# FRONT_MCU.net
KiCad netlist of a schematic drawn in Altium Designer
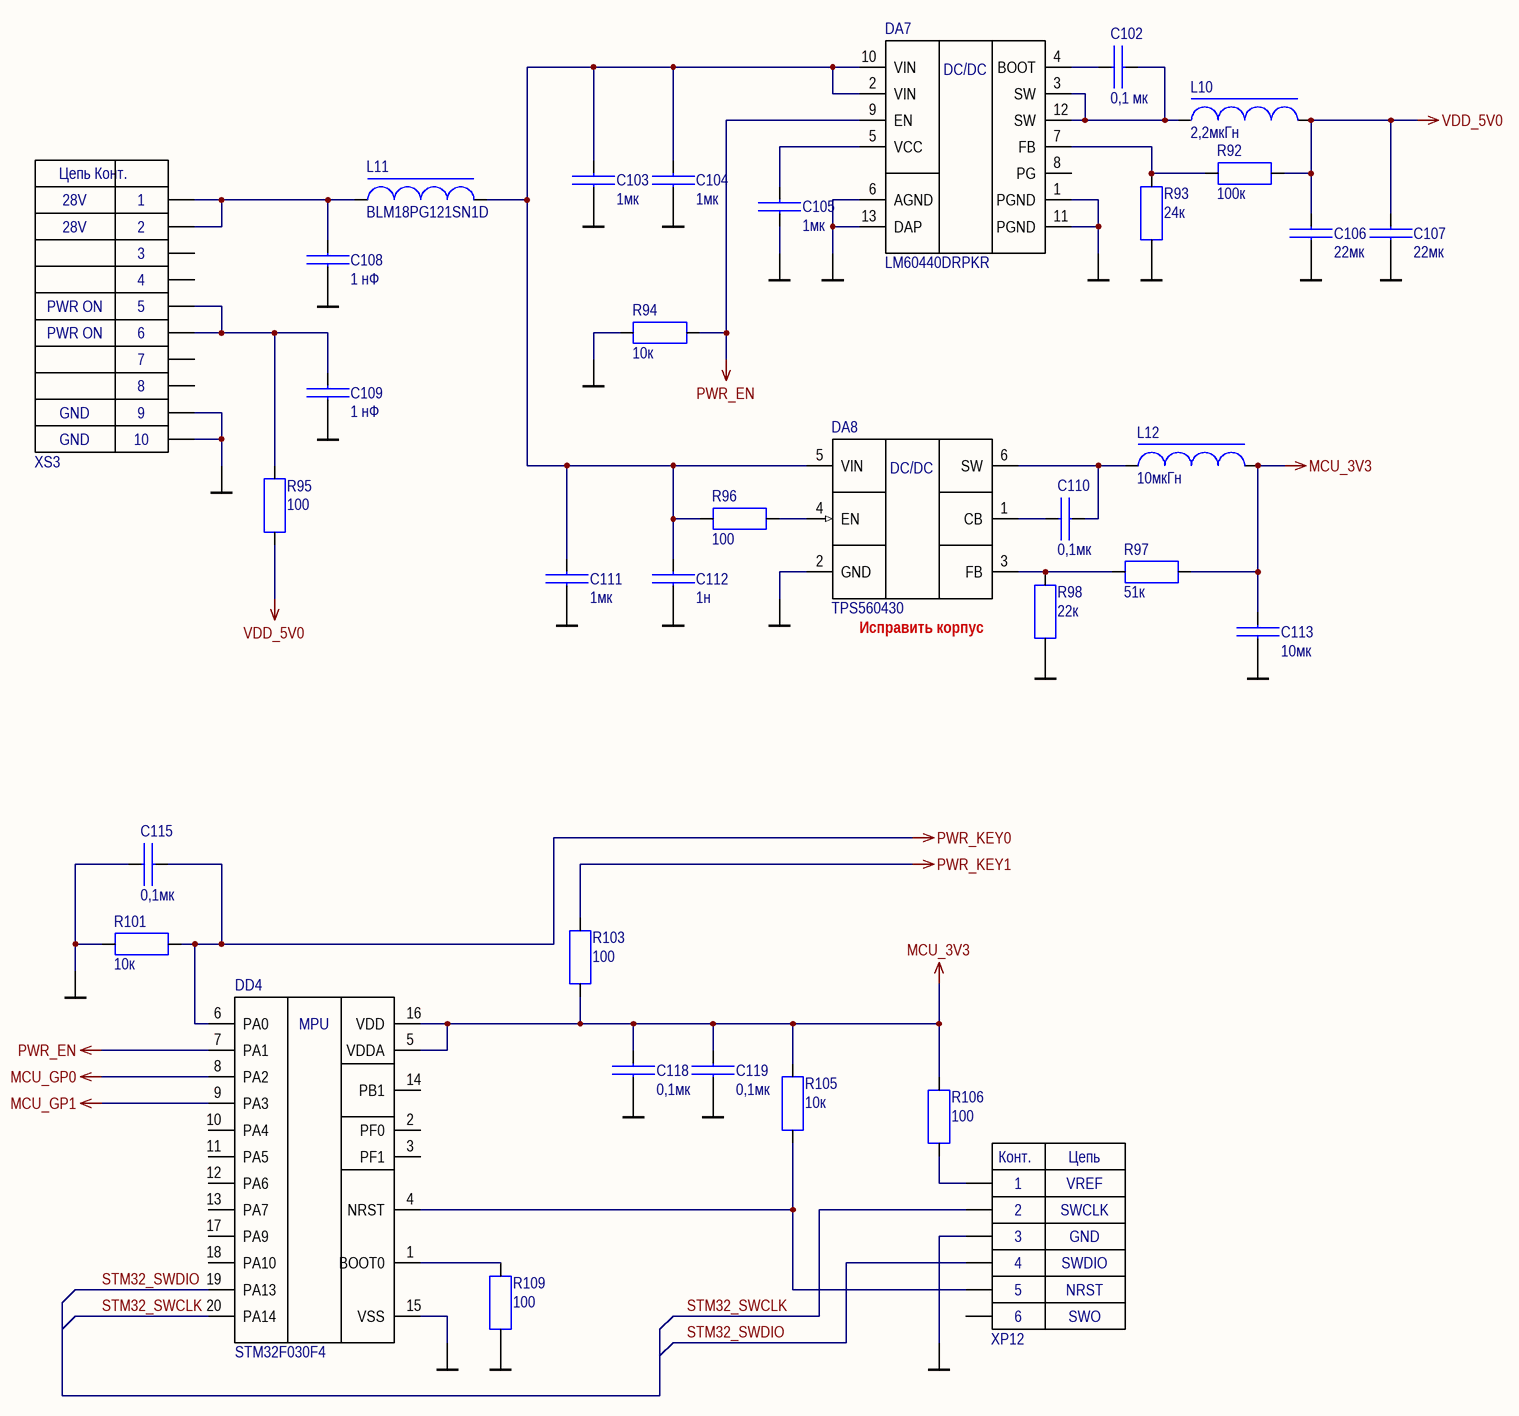
[diagram p0: FRONT_MCU.SchDoc]

(export (version "E")
  (design (tool "Eeschema 10.0.6"))
  (components
    (comp (ref "C102")
      (value "CC0402KRX5R6BB104")
      (footprint "CAPC1005X05L")
      (description "ЧИП конденсатор")
      (fields
        (field (name "NOMINAL") "0,1 мк")
        (field (name "MANUFACTURER") "Yageo")
        (field (name "TOLERANCE") "10%")
      )
      (libsource (lib "Database_Gost") (part "Capacitor const"))
    )
    (comp (ref "C103")
      (value "CC0805KKX7R9BB105")
      (footprint "CAPC2012X09L")
      (description "ЧИП конденсатор")
      (fields
        (field (name "NOMINAL") "1мк")
        (field (name "MANUFACTURER") "Yageo")
        (field (name "TOLERANCE") "0,1")
      )
      (libsource (lib "Database_Gost") (part "Capacitor const"))
    )
    (comp (ref "C104")
      (value "CC0805KKX7R9BB105")
      (footprint "CAPC2012X09L")
      (description "ЧИП конденсатор")
      (fields
        (field (name "NOMINAL") "1мк")
        (field (name "MANUFACTURER") "Yageo")
        (field (name "TOLERANCE") "0,1")
      )
      (libsource (lib "Database_Gost") (part "Capacitor const"))
    )
    (comp (ref "C105")
      (value "CC0402KRX5R5BB105")
      (footprint "CAPC1005X05L")
      (description "ЧИП конденсатор")
      (fields
        (field (name "NOMINAL") "1мк")
        (field (name "MANUFACTURER") "Yageo")
        (field (name "TOLERANCE") "10%")
      )
      (libsource (lib "Database_Gost") (part "Capacitor const"))
    )
    (comp (ref "C106")
      (value "CC0805MKX5R5BB226")
      (footprint "CAPC2012X09L")
      (description "ЧИП конденсатор")
      (fields
        (field (name "NOMINAL") "22мк")
        (field (name "MANUFACTURER") "Yageo")
        (field (name "TOLERANCE") "0,2")
      )
      (libsource (lib "Database_Gost") (part "Capacitor const"))
    )
    (comp (ref "C107")
      (value "CC0805MKX5R5BB226")
      (footprint "CAPC2012X09L")
      (description "ЧИП конденсатор")
      (fields
        (field (name "NOMINAL") "22мк")
        (field (name "MANUFACTURER") "Yageo")
        (field (name "TOLERANCE") "0,2")
      )
      (libsource (lib "Database_Gost") (part "Capacitor const"))
    )
    (comp (ref "C108")
      (value "~")
      (footprint "CAPC1005X05L")
      (description "ЧИП конденсатор")
      (fields
        (field (name "NOMINAL") "1 нФ")
        (field (name "MANUFACTURER") "Yageo")
        (field (name "MANUFACTURERPARTNUMBER") "C0402C102J5GACTU")
      )
      (libsource (lib "Database_Gost") (part "Capacitor const"))
    )
    (comp (ref "C109")
      (value "~")
      (footprint "CAPC1005X05L")
      (description "ЧИП конденсатор")
      (fields
        (field (name "NOMINAL") "1 нФ")
        (field (name "MANUFACTURER") "Yageo")
        (field (name "MANUFACTURERPARTNUMBER") "C0402C102J5GACTU")
      )
      (libsource (lib "Database_Gost") (part "Capacitor const"))
    )
    (comp (ref "C110")
      (value "CC0603KRX7R9BB103")
      (footprint "CAPC1608X08L")
      (description "ЧИП конденсатор")
      (fields
        (field (name "NOMINAL") "0,1мк")
        (field (name "MANUFACTURER") "Yageo")
        (field (name "TOLERANCE") "10%")
      )
      (libsource (lib "Database_Gost") (part "Capacitor const"))
    )
    (comp (ref "C111")
      (value "CC0805KKX7R9BB105")
      (footprint "CAPC2012X09L")
      (description "ЧИП конденсатор")
      (fields
        (field (name "NOMINAL") "1мк")
        (field (name "MANUFACTURER") "Yageo")
        (field (name "TOLERANCE") "0,1")
      )
      (libsource (lib "Database_Gost") (part "Capacitor const"))
    )
    (comp (ref "C112")
      (value "C0402C102J5GACTU")
      (footprint "CAPC1005X05L")
      (description "ЧИП конденсатор")
      (fields
        (field (name "NOMINAL") "1н")
        (field (name "MANUFACTURER") "Yageo")
        (field (name "TOLERANCE") "5%")
      )
      (libsource (lib "Database_Gost") (part "Capacitor const"))
    )
    (comp (ref "C113")
      (value "CC0805KKX5R8BB106")
      (footprint "CAPC2012X09L")
      (description "ЧИП конденсатор")
      (fields
        (field (name "NOMINAL") "10мк")
        (field (name "MANUFACTURER") "Yageo")
        (field (name "TOLERANCE") "0,1")
      )
      (libsource (lib "Database_Gost") (part "Capacitor const"))
    )
    (comp (ref "C115")
      (value "CC0402KRX5R6BB104")
      (footprint "CAPC1005X05L")
      (description "ЧИП конденсатор")
      (fields
        (field (name "NOMINAL") "0,1мк")
        (field (name "MANUFACTURER") "Yageo")
        (field (name "TOLERANCE") "10%")
      )
      (libsource (lib "Database_Gost") (part "Capacitor const"))
    )
    (comp (ref "C118")
      (value "CC0402KRX5R6BB104")
      (footprint "CAPC1005X05L")
      (description "ЧИП конденсатор")
      (fields
        (field (name "NOMINAL") "0,1мк")
        (field (name "MANUFACTURER") "Yageo")
        (field (name "TOLERANCE") "10%")
      )
      (libsource (lib "Database_Gost") (part "Capacitor const"))
    )
    (comp (ref "C119")
      (value "CC0402KRX5R6BB104")
      (footprint "CAPC1005X05L")
      (description "ЧИП конденсатор")
      (fields
        (field (name "NOMINAL") "0,1мк")
        (field (name "MANUFACTURER") "Yageo")
        (field (name "TOLERANCE") "10%")
      )
      (libsource (lib "Database_Gost") (part "Capacitor const"))
    )
    (comp (ref "DA7")
      (value "LM60440DRPKR")
      (footprint "WQFN-13")
      (description "3.8-V to 36-V, 4-A Ultra-Small Synchronous Step-Down Converter")
      (fields (field (name "MANUFACTURER") "TI"))
      (libsource (lib "Chips_single") (part "LM60440DRPKR"))
    )
    (comp (ref "DA8")
      (value "TPS560430")
      (footprint "TSOP65P280X110-8L")
      (description "SIMPLE SWITCHER® 4-V to 36-V, 600-mA Synchronous Step-Down Converter")
      (fields (field (name "MANUFACTURER") "TI"))
      (libsource (lib "Chips_single") (part "TPS560430"))
    )
    (comp (ref "DD4")
      (value "STM32F030F4")
      (footprint "TSOP65P640X120-20L")
      (fields (field (name "MANUFACTURER") "STM"))
      (libsource (lib "Chips_single") (part "STM32F030F4"))
    )
    (comp (ref "L10")
      (value "XGL4020-222ME")
      (footprint "INDCXGL4020")
      (description "Shielded Power Inductors")
      (fields (field (name "NOMINAL") "2,2мкГн") (field (name "MANUFACTURER") "Coilcraft"))
      (libsource (lib "Database_Gost") (part "Inductor ferr"))
    )
    (comp (ref "L11")
      (value "BLM18PG121SN1D")
      (footprint "INDC1608X05L")
      (description "Chip Ferrite Beads (0603 Size)")
      (fields (field (name "NOMINAL") "BLM18PG121SN1D") (field (name "MANUFACTURER") "Murata"))
      (libsource (lib "Database_Gost") (part "Inductor ferr"))
    )
    (comp (ref "L12")
      (value "1812PS-103KR")
      (footprint "INDC1812PS")
      (description "Shielded High SRF Inductors")
      (fields (field (name "NOMINAL") "10мкГн") (field (name "MANUFACTURER") "Coilcraft"))
      (libsource (lib "Database_Gost") (part "Inductor ferr"))
    )
    (comp (ref "R92")
      (value "RC0402JR-07100KL")
      (footprint "RESC1005X04L")
      (description "ЧИП резистор")
      (fields
        (field (name "NOMINAL") "100к")
        (field (name "MANUFACTURER") "Yageo")
        (field (name "TOLERANCE") "5%")
      )
      (libsource (lib "Database_Gost") (part "Resistor const"))
    )
    (comp (ref "R93")
      (value "RC0402JR-0724KL")
      (footprint "RESC1005X04L")
      (description "ЧИП резистор")
      (fields
        (field (name "NOMINAL") "24к")
        (field (name "MANUFACTURER") "Yageo")
        (field (name "TOLERANCE") "5%")
      )
      (libsource (lib "Database_Gost") (part "Resistor const"))
    )
    (comp (ref "R94")
      (value "RC0402JR-0710KL")
      (footprint "RESC1005X04L")
      (description "ЧИП резистор")
      (fields
        (field (name "NOMINAL") "10к")
        (field (name "MANUFACTURER") "Yageo")
        (field (name "TOLERANCE") "5%")
      )
      (libsource (lib "Database_Gost") (part "Resistor const"))
    )
    (comp (ref "R95")
      (value "RC0402JR-07100RL")
      (footprint "RESC1005X04L")
      (description "ЧИП резистор")
      (fields
        (field (name "NOMINAL") "100")
        (field (name "MANUFACTURER") "Yageo")
        (field (name "TOLERANCE") "5%")
      )
      (libsource (lib "Database_Gost") (part "Resistor const"))
    )
    (comp (ref "R96")
      (value "RC0402JR-07100RL")
      (footprint "RESC1005X04L")
      (description "ЧИП резистор")
      (fields
        (field (name "NOMINAL") "100")
        (field (name "MANUFACTURER") "Yageo")
        (field (name "TOLERANCE") "5%")
      )
      (libsource (lib "Database_Gost") (part "Resistor const"))
    )
    (comp (ref "R97")
      (value "RC0402JR-0751KL")
      (footprint "RESC1005X04L")
      (description "ЧИП резистор")
      (fields
        (field (name "NOMINAL") "51к")
        (field (name "MANUFACTURER") "Yageo")
        (field (name "TOLERANCE") "5%")
      )
      (libsource (lib "Database_Gost") (part "Resistor const"))
    )
    (comp (ref "R98")
      (value "RC0402JR-0722KL")
      (footprint "RESC1005X04L")
      (description "ЧИП резистор")
      (fields
        (field (name "NOMINAL") "22к")
        (field (name "MANUFACTURER") "Yageo")
        (field (name "TOLERANCE") "5%")
      )
      (libsource (lib "Database_Gost") (part "Resistor const"))
    )
    (comp (ref "R101")
      (value "RC0402JR-0710KL")
      (footprint "RESC1005X04L")
      (description "ЧИП резистор")
      (fields
        (field (name "NOMINAL") "10к")
        (field (name "MANUFACTURER") "Yageo")
        (field (name "TOLERANCE") "5%")
      )
      (libsource (lib "Database_Gost") (part "Resistor const"))
    )
    (comp (ref "R103")
      (value "RC0402JR-07100RL")
      (footprint "RESC1005X04L")
      (description "ЧИП резистор")
      (fields
        (field (name "NOMINAL") "100")
        (field (name "MANUFACTURER") "Yageo")
        (field (name "TOLERANCE") "5%")
      )
      (libsource (lib "Database_Gost") (part "Resistor const"))
    )
    (comp (ref "R105")
      (value "RC0402JR-0710KL")
      (footprint "RESC1005X04L")
      (description "ЧИП резистор")
      (fields
        (field (name "NOMINAL") "10к")
        (field (name "MANUFACTURER") "Yageo")
        (field (name "TOLERANCE") "5%")
      )
      (libsource (lib "Database_Gost") (part "Resistor const"))
    )
    (comp (ref "R106")
      (value "RC0402JR-07100RL")
      (footprint "RESC1005X04L")
      (description "ЧИП резистор")
      (fields
        (field (name "NOMINAL") "100")
        (field (name "MANUFACTURER") "Yageo")
        (field (name "TOLERANCE") "5%")
      )
      (libsource (lib "Database_Gost") (part "Resistor const"))
    )
    (comp (ref "R109")
      (value "RC0402JR-07100RL")
      (footprint "RESC1005X04L")
      (description "ЧИП резистор")
      (fields
        (field (name "NOMINAL") "100")
        (field (name "MANUFACTURER") "Yageo")
        (field (name "TOLERANCE") "5%")
      )
      (libsource (lib "Database_Gost") (part "Resistor const"))
    )
    (comp (ref "XP12")
      (value "PLS-6")
      (footprint "HDR1X6")
      (libsource (lib "Connectors") (part "STM32 S-LINK PLS-6"))
    )
    (comp (ref "XS3")
      (value "FH12-10S-0.5SVA")
      (footprint "FH12-10S-0.5SH")
      (fields (field (name "MANUFACTURER") "Hirose"))
      (libsource (lib "Connectors") (part "FH12-10S-0.5SVA"))
    )
  )
  (nets
    (net (code "1") (name "/STM32_SWCLK") (class "Default")
      (node (ref "DD4") (pin "20") (pinfunction "PA14_20") (pintype "passive"))
      (node (ref "XP12") (pin "2") (pinfunction "2_2") (pintype "passive"))
    )
    (net (code "2") (name "/STM32_SWDIO") (class "Default")
      (node (ref "DD4") (pin "19") (pinfunction "PA13_19") (pintype "passive"))
      (node (ref "XP12") (pin "4") (pinfunction "4_4") (pintype "passive"))
    )
    (net (code "3") (name "GND") (class "Default")
      (node (ref "C103") (pin "1") (pinfunction "1_1") (pintype "passive"))
      (node (ref "C104") (pin "1") (pinfunction "1_1") (pintype "passive"))
      (node (ref "C105") (pin "1") (pinfunction "1_1") (pintype "passive"))
      (node (ref "C106") (pin "1") (pinfunction "1_1") (pintype "passive"))
      (node (ref "C107") (pin "1") (pinfunction "1_1") (pintype "passive"))
      (node (ref "C108") (pin "1") (pinfunction "1_1") (pintype "passive"))
      (node (ref "C109") (pin "1") (pinfunction "1_1") (pintype "passive"))
      (node (ref "C111") (pin "2") (pinfunction "2_2") (pintype "passive"))
      (node (ref "C112") (pin "2") (pinfunction "2_2") (pintype "passive"))
      (node (ref "C113") (pin "1") (pinfunction "1_1") (pintype "passive"))
      (node (ref "C115") (pin "1") (pinfunction "1_1") (pintype "passive"))
      (node (ref "C118") (pin "2") (pinfunction "2_2") (pintype "passive"))
      (node (ref "C119") (pin "2") (pinfunction "2_2") (pintype "passive"))
      (node (ref "DA7") (pin "1") (pinfunction "PGND_1") (pintype "passive"))
      (node (ref "DA7") (pin "11") (pinfunction "PGND_11") (pintype "passive"))
      (node (ref "DA7") (pin "13") (pinfunction "DAP_13") (pintype "passive"))
      (node (ref "DA7") (pin "6") (pinfunction "AGND_6") (pintype "passive"))
      (node (ref "DA8") (pin "2") (pinfunction "GND_2") (pintype "passive"))
      (node (ref "DD4") (pin "15") (pinfunction "VSS_15") (pintype "passive"))
      (node (ref "R101") (pin "2") (pinfunction "2_2") (pintype "passive"))
      (node (ref "R109") (pin "1") (pinfunction "1_1") (pintype "passive"))
      (node (ref "R93") (pin "2") (pinfunction "2_2") (pintype "passive"))
      (node (ref "R94") (pin "2") (pinfunction "2_2") (pintype "passive"))
      (node (ref "R98") (pin "1") (pinfunction "1_1") (pintype "passive"))
      (node (ref "XP12") (pin "3") (pinfunction "3_3") (pintype "passive"))
      (node (ref "XS3") (pin "10") (pinfunction "10_10") (pintype "passive"))
      (node (ref "XS3") (pin "9") (pinfunction "9_9") (pintype "passive"))
    )
    (net (code "4") (name "MCU_3V3") (class "Default")
      (node (ref "C113") (pin "2") (pinfunction "2_2") (pintype "passive"))
      (node (ref "C118") (pin "1") (pinfunction "1_1") (pintype "passive"))
      (node (ref "C119") (pin "1") (pinfunction "1_1") (pintype "passive"))
      (node (ref "DD4") (pin "16") (pinfunction "VDD_16") (pintype "passive"))
      (node (ref "DD4") (pin "5") (pinfunction "VDDA_5") (pintype "passive"))
      (node (ref "L12") (pin "1") (pinfunction "1_1") (pintype "passive"))
      (node (ref "R103") (pin "1") (pinfunction "1_1") (pintype "passive"))
      (node (ref "R105") (pin "2") (pinfunction "2_2") (pintype "passive"))
      (node (ref "R106") (pin "2") (pinfunction "2_2") (pintype "passive"))
      (node (ref "R97") (pin "1") (pinfunction "1_1") (pintype "passive"))
    )
    (net (code "5") (name "MCU_GP0") (class "Default")
      (node (ref "DD4") (pin "8") (pinfunction "PA2_8") (pintype "passive"))
    )
    (net (code "6") (name "MCU_GP1") (class "Default")
      (node (ref "DD4") (pin "9") (pinfunction "PA3_9") (pintype "passive"))
    )
    (net (code "7") (name "Net-(C102-Pad2)") (class "Default")
      (node (ref "C102") (pin "2") (pinfunction "2_2") (pintype "passive"))
      (node (ref "DA7") (pin "12") (pinfunction "SW_12") (pintype "passive"))
      (node (ref "DA7") (pin "3") (pinfunction "SW_3") (pintype "passive"))
      (node (ref "L10") (pin "2") (pinfunction "2_2") (pintype "passive"))
    )
    (net (code "8") (name "Net-(C108-Pad2)") (class "Default")
      (node (ref "C108") (pin "2") (pinfunction "2_2") (pintype "passive"))
      (node (ref "L11") (pin "2") (pinfunction "2_2") (pintype "passive"))
      (node (ref "XS3") (pin "1") (pinfunction "1_1") (pintype "passive"))
      (node (ref "XS3") (pin "2") (pinfunction "2_2") (pintype "passive"))
    )
    (net (code "9") (name "Net-(C109-Pad2)") (class "Default")
      (node (ref "C109") (pin "2") (pinfunction "2_2") (pintype "passive"))
      (node (ref "R95") (pin "2") (pinfunction "2_2") (pintype "passive"))
      (node (ref "XS3") (pin "5") (pinfunction "5_5") (pintype "passive"))
      (node (ref "XS3") (pin "6") (pinfunction "6_6") (pintype "passive"))
    )
    (net (code "10") (name "Net-(DA7-BOOT)") (class "Default")
      (node (ref "C102") (pin "1") (pinfunction "1_1") (pintype "passive"))
      (node (ref "DA7") (pin "4") (pinfunction "BOOT_4") (pintype "passive"))
    )
    (net (code "11") (name "Net-(DA7-FB)") (class "Default")
      (node (ref "DA7") (pin "7") (pinfunction "FB_7") (pintype "passive"))
      (node (ref "R92") (pin "2") (pinfunction "2_2") (pintype "passive"))
      (node (ref "R93") (pin "1") (pinfunction "1_1") (pintype "passive"))
    )
    (net (code "12") (name "Net-(DA7-VCC)") (class "Default")
      (node (ref "C105") (pin "2") (pinfunction "2_2") (pintype "passive"))
      (node (ref "DA7") (pin "5") (pinfunction "VCC_5") (pintype "passive"))
    )
    (net (code "13") (name "Net-(DA8-CB)") (class "Default")
      (node (ref "C110") (pin "1") (pinfunction "1_1") (pintype "passive"))
      (node (ref "DA8") (pin "1") (pinfunction "CB_1") (pintype "passive"))
    )
    (net (code "14") (name "Net-(DA8-EN)") (class "Default")
      (node (ref "DA8") (pin "4") (pinfunction "EN_4") (pintype "input"))
      (node (ref "R96") (pin "2") (pinfunction "2_2") (pintype "passive"))
    )
    (net (code "15") (name "Net-(DA8-FB)") (class "Default")
      (node (ref "DA8") (pin "3") (pinfunction "FB_3") (pintype "passive"))
      (node (ref "R97") (pin "2") (pinfunction "2_2") (pintype "passive"))
      (node (ref "R98") (pin "2") (pinfunction "2_2") (pintype "passive"))
    )
    (net (code "16") (name "Net-(DA8-SW)") (class "Default")
      (node (ref "C110") (pin "2") (pinfunction "2_2") (pintype "passive"))
      (node (ref "DA8") (pin "6") (pinfunction "SW_6") (pintype "passive"))
      (node (ref "L12") (pin "2") (pinfunction "2_2") (pintype "passive"))
    )
    (net (code "17") (name "Net-(DA8-VIN)") (class "Default")
      (node (ref "C103") (pin "2") (pinfunction "2_2") (pintype "passive"))
      (node (ref "C104") (pin "2") (pinfunction "2_2") (pintype "passive"))
      (node (ref "C111") (pin "1") (pinfunction "1_1") (pintype "passive"))
      (node (ref "C112") (pin "1") (pinfunction "1_1") (pintype "passive"))
      (node (ref "DA7") (pin "10") (pinfunction "VIN_10") (pintype "passive"))
      (node (ref "DA7") (pin "2") (pinfunction "VIN_2") (pintype "passive"))
      (node (ref "DA8") (pin "5") (pinfunction "VIN_5") (pintype "passive"))
      (node (ref "L11") (pin "1") (pinfunction "1_1") (pintype "passive"))
      (node (ref "R96") (pin "1") (pinfunction "1_1") (pintype "passive"))
    )
    (net (code "18") (name "Net-(DD4-BOOT0)") (class "Default")
      (node (ref "DD4") (pin "1") (pinfunction "BOOT0_1") (pintype "passive"))
      (node (ref "R109") (pin "2") (pinfunction "2_2") (pintype "passive"))
    )
    (net (code "19") (name "Net-(DD4-NRST)") (class "Default")
      (node (ref "DD4") (pin "4") (pinfunction "NRST_4") (pintype "passive"))
      (node (ref "R105") (pin "1") (pinfunction "1_1") (pintype "passive"))
      (node (ref "XP12") (pin "5") (pinfunction "5_5") (pintype "passive"))
    )
    (net (code "20") (name "Net-(R106-Pad1)") (class "Default")
      (node (ref "R106") (pin "1") (pinfunction "1_1") (pintype "passive"))
      (node (ref "XP12") (pin "1") (pinfunction "1_1") (pintype "passive"))
    )
    (net (code "21") (name "PWR_EN") (class "Default")
      (node (ref "DA7") (pin "9") (pinfunction "EN_9") (pintype "passive"))
      (node (ref "DD4") (pin "7") (pinfunction "PA1_7") (pintype "passive"))
      (node (ref "R94") (pin "1") (pinfunction "1_1") (pintype "passive"))
    )
    (net (code "22") (name "PWR_KEY0") (class "Default")
      (node (ref "C115") (pin "2") (pinfunction "2_2") (pintype "passive"))
      (node (ref "DD4") (pin "6") (pinfunction "PA0_6") (pintype "passive"))
      (node (ref "R101") (pin "1") (pinfunction "1_1") (pintype "passive"))
    )
    (net (code "23") (name "PWR_KEY1") (class "Default")
      (node (ref "R103") (pin "2") (pinfunction "2_2") (pintype "passive"))
    )
    (net (code "24") (name "VDD_5V0") (class "Default")
      (node (ref "C106") (pin "2") (pinfunction "2_2") (pintype "passive"))
      (node (ref "C107") (pin "2") (pinfunction "2_2") (pintype "passive"))
      (node (ref "L10") (pin "1") (pinfunction "1_1") (pintype "passive"))
      (node (ref "R92") (pin "1") (pinfunction "1_1") (pintype "passive"))
      (node (ref "R95") (pin "1") (pinfunction "1_1") (pintype "passive"))
    )
    (net (code "25") (name "unconnected-(DA7-PG-Pad8)") (class "Default")
      (node (ref "DA7") (pin "8") (pinfunction "PG_8") (pintype "passive"))
    )
    (net (code "26") (name "unconnected-(DD4-PA4-Pad10)") (class "Default")
      (node (ref "DD4") (pin "10") (pinfunction "PA4_10") (pintype "passive"))
    )
    (net (code "27") (name "unconnected-(DD4-PA5-Pad11)") (class "Default")
      (node (ref "DD4") (pin "11") (pinfunction "PA5_11") (pintype "passive"))
    )
    (net (code "28") (name "unconnected-(DD4-PA6-Pad12)") (class "Default")
      (node (ref "DD4") (pin "12") (pinfunction "PA6_12") (pintype "passive"))
    )
    (net (code "29") (name "unconnected-(DD4-PA7-Pad13)") (class "Default")
      (node (ref "DD4") (pin "13") (pinfunction "PA7_13") (pintype "passive"))
    )
    (net (code "30") (name "unconnected-(DD4-PA9-Pad17)") (class "Default")
      (node (ref "DD4") (pin "17") (pinfunction "PA9_17") (pintype "passive"))
    )
    (net (code "31") (name "unconnected-(DD4-PA10-Pad18)") (class "Default")
      (node (ref "DD4") (pin "18") (pinfunction "PA10_18") (pintype "passive"))
    )
    (net (code "32") (name "unconnected-(DD4-PB1-Pad14)") (class "Default")
      (node (ref "DD4") (pin "14") (pinfunction "PB1_14") (pintype "passive"))
    )
    (net (code "33") (name "unconnected-(DD4-PF0-Pad2)") (class "Default")
      (node (ref "DD4") (pin "2") (pinfunction "PF0_2") (pintype "passive"))
    )
    (net (code "34") (name "unconnected-(DD4-PF1-Pad3)") (class "Default")
      (node (ref "DD4") (pin "3") (pinfunction "PF1_3") (pintype "passive"))
    )
    (net (code "35") (name "unconnected-(XP12-Pad6)") (class "Default")
      (node (ref "XP12") (pin "6") (pinfunction "6_6") (pintype "passive"))
    )
    (net (code "36") (name "unconnected-(XS3-Pad3)") (class "Default")
      (node (ref "XS3") (pin "3") (pinfunction "3_3") (pintype "passive"))
    )
    (net (code "37") (name "unconnected-(XS3-Pad4)") (class "Default")
      (node (ref "XS3") (pin "4") (pinfunction "4_4") (pintype "passive"))
    )
    (net (code "38") (name "unconnected-(XS3-Pad7)") (class "Default")
      (node (ref "XS3") (pin "7") (pinfunction "7_7") (pintype "passive"))
    )
    (net (code "39") (name "unconnected-(XS3-Pad8)") (class "Default")
      (node (ref "XS3") (pin "8") (pinfunction "8_8") (pintype "passive"))
    )
  )
)
